# battery.net
KiCad netlist of a schematic drawn in Altium Designer
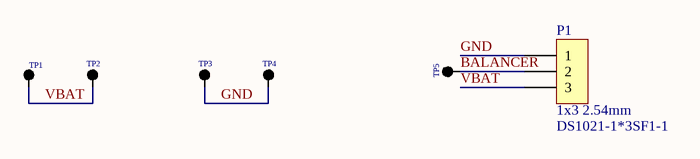
[diagram p0: battery.SchDoc]

(export (version "E")
  (design (tool "Eeschema 10.0.6"))
  (components
    (comp (ref "P1")
      (value "DS1021-1*3SF1-1")
      (footprint "P_HEADER_1x3_2.54")
      (description "Pin Header")
      (fields
        (field (name "SCH_FOOTPRINT") "1x3 2.54mm")
        (field (name "PART NUMBER") "P_HEADER_1x3_2.54")
        (field (name "MANUFACTURER") "Connfly")
      )
      (libsource (lib "Library") (part "P_HEADER_1x3"))
    )
    (comp (ref "TP1")
      (value "SMD pad")
      (footprint "TP_PAD")
      (description "Testpoint")
      (fields (field (name "PART NUMBER") "TP_PAD"))
      (libsource (lib "Library") (part "TP_TESTPOINT"))
    )
    (comp (ref "TP2")
      (value "SMD pad")
      (footprint "TP_PAD")
      (description "Testpoint")
      (fields (field (name "PART NUMBER") "TP_PAD"))
      (libsource (lib "Library") (part "TP_TESTPOINT"))
    )
    (comp (ref "TP3")
      (value "SMD pad")
      (footprint "TP_PAD")
      (description "Testpoint")
      (fields (field (name "PART NUMBER") "TP_PAD"))
      (libsource (lib "Library") (part "TP_TESTPOINT"))
    )
    (comp (ref "TP4")
      (value "SMD pad")
      (footprint "TP_PAD")
      (description "Testpoint")
      (fields (field (name "PART NUMBER") "TP_PAD"))
      (libsource (lib "Library") (part "TP_TESTPOINT"))
    )
    (comp (ref "TP5")
      (value "Single pin")
      (footprint "TP_1PIN")
      (description "Testpoint")
      (fields (field (name "PART NUMBER") "TP_1PIN"))
      (libsource (lib "Library") (part "TP_TESTPOINT"))
    )
  )
  (nets
    (net (code "1") (name "/BALANCER") (class "Default")
      (node (ref "P1") (pin "2") (pinfunction "2_2") (pintype "passive"))
      (node (ref "TP5") (pin "1") (pinfunction "TP_1") (pintype "passive"))
    )
    (net (code "2") (name "/GND") (class "Default")
      (node (ref "P1") (pin "1") (pinfunction "1_1") (pintype "passive"))
      (node (ref "TP3") (pin "1") (pinfunction "TP_1") (pintype "passive"))
      (node (ref "TP4") (pin "1") (pinfunction "TP_1") (pintype "passive"))
    )
    (net (code "3") (name "/VBAT") (class "Default")
      (node (ref "P1") (pin "3") (pinfunction "3_3") (pintype "passive"))
      (node (ref "TP1") (pin "1") (pinfunction "TP_1") (pintype "passive"))
      (node (ref "TP2") (pin "1") (pinfunction "TP_1") (pintype "passive"))
    )
  )
)
